# Communication.net
KiCad netlist of a schematic drawn in Altium Designer
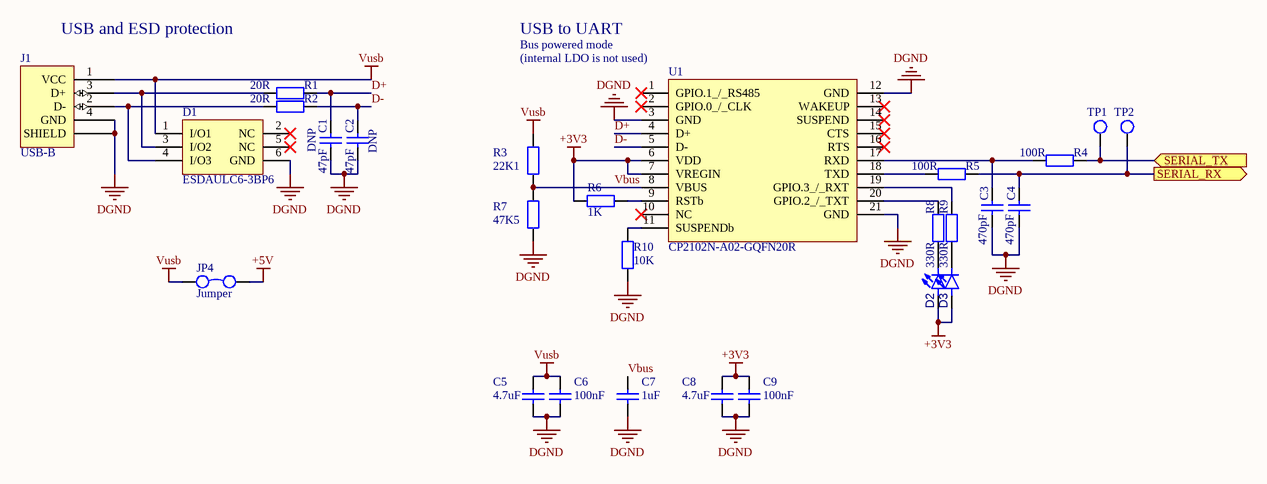
[diagram p0: Communication.SchDoc]

(export (version "E")
  (design (tool "Eeschema 10.0.6"))
  (components
    (comp (ref "C1")
      (value "DNP")
      (footprint "CAP0603")
      (fields
        (field (name "MANUFACTURER") "KEMET")
        (field (name "MANUFACTURER PART NUMBER") "C0603C470J1GACTU")
        (field (name "ALTIUM_VALUE") "47pF")
      )
      (libsource (lib "UPS_Schlib") (part "47pF"))
    )
    (comp (ref "C2")
      (value "DNP")
      (footprint "CAP0603")
      (fields
        (field (name "MANUFACTURER") "KEMET")
        (field (name "MANUFACTURER PART NUMBER") "C0603C470J1GACTU")
        (field (name "ALTIUM_VALUE") "47pF")
      )
      (libsource (lib "UPS_Schlib") (part "47pF"))
    )
    (comp (ref "C3")
      (value "470pF")
      (footprint "CAP0603")
      (fields
        (field (name "MANUFACTURER") "KEMET")
        (field (name "MANUFACTURER PART NUMBER") "C0603C471JAGACAUTO")
      )
      (libsource (lib "UPS_Schlib") (part "470pF"))
    )
    (comp (ref "C4")
      (value "470pF")
      (footprint "CAP0603")
      (fields
        (field (name "MANUFACTURER") "KEMET")
        (field (name "MANUFACTURER PART NUMBER") "C0603C471JAGACAUTO")
      )
      (libsource (lib "UPS_Schlib") (part "470pF"))
    )
    (comp (ref "C5")
      (value "4.7uF")
      (footprint "CAP0603")
      (description "Capacitor")
      (libsource (lib "UPS_Schlib") (part "4.7uF"))
    )
    (comp (ref "C6")
      (value "100nF")
      (footprint "CAP0603")
      (description "Capacitor")
      (libsource (lib "UPS_Schlib") (part "100nF"))
    )
    (comp (ref "C7")
      (value "1uF")
      (footprint "CAP0603")
      (description "Capacitor")
      (libsource (lib "UPS_Schlib") (part "1uF"))
    )
    (comp (ref "C8")
      (value "4.7uF")
      (footprint "CAP0603")
      (description "Capacitor")
      (libsource (lib "UPS_Schlib") (part "4.7uF"))
    )
    (comp (ref "C9")
      (value "100nF")
      (footprint "CAP0603")
      (description "Capacitor")
      (libsource (lib "UPS_Schlib") (part "100nF"))
    )
    (comp (ref "D1")
      (value "ESDAULC6-3BP6")
      (footprint "SOT-666")
      (description "TVS Diode (Bi-directional)")
      (fields (field (name "MOUSER PART NUMBER") "511-ESDAULC63BP6"))
      (libsource (lib "UPS_Schlib") (part "ESDAULC6-3BP6"))
    )
    (comp (ref "D2")
      (value "~")
      (footprint "LED0603")
      (description "Single Color LED, Bright Green, Water Clear, 1.1mm")
      (fields
        (field (name "MANUFACTURER") "Wurth Electronics")
        (field (name "MANUFACTURER PART NUMBER") "150060VS75000")
      )
      (libsource (lib "UPS_Schlib") (part "LED Green"))
    )
    (comp (ref "D3")
      (value "~")
      (footprint "LED0603")
      (description "Single Color LED, Bright Green, Water Clear, 1.1mm")
      (fields
        (field (name "MANUFACTURER") "Wurth Electronics")
        (field (name "MANUFACTURER PART NUMBER") "150060VS75000")
      )
      (libsource (lib "UPS_Schlib") (part "LED Green"))
    )
    (comp (ref "J1")
      (value "USB-B")
      (footprint "USB-B-FEMALE")
      (description "USB Connector")
      (libsource (lib "UPS_Schlib") (part "USB-B"))
    )
    (comp (ref "JP4")
      (value "Jumper")
      (footprint "PIN-1X2")
      (description "2 pin jumper connection")
      (libsource (lib "UPS_Schlib") (part "Jumper"))
    )
    (comp (ref "R1")
      (value "20R")
      (footprint "RES0603")
      (description "Resistor")
      (libsource (lib "UPS_Schlib") (part "20R"))
    )
    (comp (ref "R2")
      (value "20R")
      (footprint "RES0603")
      (description "Resistor")
      (libsource (lib "UPS_Schlib") (part "20R"))
    )
    (comp (ref "R3")
      (value "22K1")
      (footprint "RES0603")
      (description "Resistor")
      (libsource (lib "UPS_Schlib") (part "22K1"))
    )
    (comp (ref "R4")
      (value "100R")
      (footprint "RES0603")
      (description "Resistor")
      (libsource (lib "UPS_Schlib") (part "100R"))
    )
    (comp (ref "R5")
      (value "100R")
      (footprint "RES0603")
      (description "Resistor")
      (libsource (lib "UPS_Schlib") (part "100R"))
    )
    (comp (ref "R6")
      (value "1K")
      (footprint "RES0603")
      (description "Resistor")
      (libsource (lib "UPS_Schlib") (part "1K"))
    )
    (comp (ref "R7")
      (value "47K5")
      (footprint "RES0603")
      (description "Resistor")
      (libsource (lib "UPS_Schlib") (part "47K5"))
    )
    (comp (ref "R8")
      (value "330R")
      (footprint "RES0603")
      (description "Resistor")
      (libsource (lib "UPS_Schlib") (part "330R"))
    )
    (comp (ref "R9")
      (value "330R")
      (footprint "RES0603")
      (description "Resistor")
      (libsource (lib "UPS_Schlib") (part "330R"))
    )
    (comp (ref "R10")
      (value "10K")
      (footprint "RES0603")
      (description "Resistor")
      (libsource (lib "UPS_Schlib") (part "10K"))
    )
    (comp (ref "TP1")
      (value "Test Point")
      (footprint "TP-1.5HOLE")
      (libsource (lib "UPS_Schlib") (part "Test Point"))
    )
    (comp (ref "TP2")
      (value "Test Point")
      (footprint "TP-1.5HOLE")
      (libsource (lib "UPS_Schlib") (part "Test Point"))
    )
    (comp (ref "U1")
      (value "CP2102N-A02-GQFN20R")
      (footprint "QFN-20")
      (description "USB-UART Bridge")
      (fields (field (name "MOUSER PART NUMBER") "634-CP2102NA02QFN20R"))
      (libsource (lib "UPS_Schlib") (part "CP2102N-A02-GQFN20R"))
    )
  )
  (nets
    (net (code "1") (name "+3V3") (class "Default")
      (node (ref "C8") (pin "2") (pinfunction "2_2") (pintype "passive"))
      (node (ref "C9") (pin "1") (pinfunction "1_1") (pintype "passive"))
      (node (ref "D2") (pin "2") (pinfunction "A_2") (pintype "passive"))
      (node (ref "D3") (pin "2") (pinfunction "A_2") (pintype "passive"))
      (node (ref "R6") (pin "1") (pinfunction "1_1") (pintype "passive"))
      (node (ref "U1") (pin "6") (pinfunction "VDD_6") (pintype "passive"))
      (node (ref "U1") (pin "7") (pinfunction "VREGIN_7") (pintype "passive"))
    )
    (net (code "2") (name "+5V") (class "Default") (node (ref "JP4") (pin "2") (pintype "passive")))
    (net (code "3") (name "/D+") (class "Default")
      (node (ref "C1") (pin "2") (pinfunction "2_2") (pintype "passive"))
      (node (ref "R1") (pin "1") (pinfunction "1_1") (pintype "passive"))
      (node (ref "U1") (pin "4") (pinfunction "D+_4") (pintype "passive"))
    )
    (net (code "4") (name "/D-") (class "Default")
      (node (ref "C2") (pin "2") (pinfunction "2_2") (pintype "passive"))
      (node (ref "R2") (pin "1") (pinfunction "1_1") (pintype "passive"))
      (node (ref "U1") (pin "5") (pinfunction "D-_5") (pintype "passive"))
    )
    (net (code "5") (name "/SERIAL_RX") (class "Default")
      (node (ref "C4") (pin "2") (pinfunction "2_2") (pintype "passive"))
      (node (ref "R5") (pin "2") (pinfunction "2_2") (pintype "passive"))
      (node (ref "TP2") (pin "1") (pintype "passive"))
    )
    (net (code "6") (name "/SERIAL_TX") (class "Default")
      (node (ref "R4") (pin "2") (pinfunction "2_2") (pintype "passive"))
      (node (ref "TP1") (pin "1") (pintype "passive"))
    )
    (net (code "7") (name "/Vbus") (class "Default")
      (node (ref "C7") (pin "2") (pinfunction "2_2") (pintype "passive"))
      (node (ref "R3") (pin "1") (pinfunction "1_1") (pintype "passive"))
      (node (ref "R7") (pin "2") (pinfunction "2_2") (pintype "passive"))
      (node (ref "U1") (pin "8") (pinfunction "VBUS_8") (pintype "passive"))
    )
    (net (code "8") (name "DGND") (class "Default")
      (node (ref "C1") (pin "1") (pinfunction "1_1") (pintype "passive"))
      (node (ref "C2") (pin "1") (pinfunction "1_1") (pintype "passive"))
      (node (ref "C3") (pin "1") (pinfunction "1_1") (pintype "passive"))
      (node (ref "C4") (pin "1") (pinfunction "1_1") (pintype "passive"))
      (node (ref "C5") (pin "1") (pinfunction "1_1") (pintype "passive"))
      (node (ref "C6") (pin "2") (pinfunction "2_2") (pintype "passive"))
      (node (ref "C7") (pin "1") (pinfunction "1_1") (pintype "passive"))
      (node (ref "C8") (pin "1") (pinfunction "1_1") (pintype "passive"))
      (node (ref "C9") (pin "2") (pinfunction "2_2") (pintype "passive"))
      (node (ref "D1") (pin "6") (pinfunction "GND_6") (pintype "passive"))
      (node (ref "J1") (pin "0") (pinfunction "SHIELD_0") (pintype "passive"))
      (node (ref "J1") (pin "4") (pinfunction "GND_4") (pintype "passive"))
      (node (ref "R10") (pin "1") (pinfunction "1_1") (pintype "passive"))
      (node (ref "R7") (pin "1") (pinfunction "1_1") (pintype "passive"))
      (node (ref "U1") (pin "12") (pinfunction "GND_12") (pintype "passive"))
      (node (ref "U1") (pin "21") (pinfunction "GND_21") (pintype "passive"))
      (node (ref "U1") (pin "3") (pinfunction "GND_3") (pintype "passive"))
    )
    (net (code "9") (name "Net-(D1-I{slash}O2)") (class "Default")
      (node (ref "D1") (pin "3") (pinfunction "I/O2_3") (pintype "passive"))
      (node (ref "J1") (pin "3") (pinfunction "D+_3") (pintype "bidirectional"))
      (node (ref "R1") (pin "2") (pinfunction "2_2") (pintype "passive"))
    )
    (net (code "10") (name "Net-(D1-I{slash}O3)") (class "Default")
      (node (ref "D1") (pin "4") (pinfunction "I/O3_4") (pintype "passive"))
      (node (ref "J1") (pin "2") (pinfunction "D-_2") (pintype "bidirectional"))
      (node (ref "R2") (pin "2") (pinfunction "2_2") (pintype "passive"))
    )
    (net (code "11") (name "Net-(D2-K)") (class "Default")
      (node (ref "D2") (pin "1") (pinfunction "K_1") (pintype "passive"))
      (node (ref "R8") (pin "2") (pinfunction "2_2") (pintype "passive"))
    )
    (net (code "12") (name "Net-(D3-K)") (class "Default")
      (node (ref "D3") (pin "1") (pinfunction "K_1") (pintype "passive"))
      (node (ref "R9") (pin "2") (pinfunction "2_2") (pintype "passive"))
    )
    (net (code "13") (name "Net-(U1-GPIO.2_{slash}_TXT)") (class "Default")
      (node (ref "R8") (pin "1") (pinfunction "1_1") (pintype "passive"))
      (node (ref "U1") (pin "20") (pinfunction "GPIO.2_/_TXT_20") (pintype "passive"))
    )
    (net (code "14") (name "Net-(U1-GPIO.3_{slash}_RXT)") (class "Default")
      (node (ref "R9") (pin "1") (pinfunction "1_1") (pintype "passive"))
      (node (ref "U1") (pin "19") (pinfunction "GPIO.3_/_RXT_19") (pintype "passive"))
    )
    (net (code "15") (name "Net-(U1-RSTb)") (class "Default")
      (node (ref "R6") (pin "2") (pinfunction "2_2") (pintype "passive"))
      (node (ref "U1") (pin "9") (pinfunction "RSTb_9") (pintype "passive"))
    )
    (net (code "16") (name "Net-(U1-RXD)") (class "Default")
      (node (ref "C3") (pin "2") (pinfunction "2_2") (pintype "passive"))
      (node (ref "R4") (pin "1") (pinfunction "1_1") (pintype "passive"))
      (node (ref "U1") (pin "17") (pinfunction "RXD_17") (pintype "passive"))
    )
    (net (code "17") (name "Net-(U1-SUSPENDb)") (class "Default")
      (node (ref "R10") (pin "2") (pinfunction "2_2") (pintype "passive"))
      (node (ref "U1") (pin "11") (pinfunction "SUSPENDb_11") (pintype "passive"))
    )
    (net (code "18") (name "Net-(U1-TXD)") (class "Default")
      (node (ref "R5") (pin "1") (pinfunction "1_1") (pintype "passive"))
      (node (ref "U1") (pin "18") (pinfunction "TXD_18") (pintype "passive"))
    )
    (net (code "19") (name "Vusb") (class "Default")
      (node (ref "C5") (pin "2") (pinfunction "2_2") (pintype "passive"))
      (node (ref "C6") (pin "1") (pinfunction "1_1") (pintype "passive"))
      (node (ref "D1") (pin "1") (pinfunction "I/O1_1") (pintype "passive"))
      (node (ref "J1") (pin "1") (pinfunction "VCC_1") (pintype "power_in"))
      (node (ref "JP4") (pin "1") (pintype "passive"))
      (node (ref "R3") (pin "2") (pinfunction "2_2") (pintype "passive"))
    )
    (net (code "20") (name "unconnected-(D1-NC-Pad2)") (class "Default")
      (node (ref "D1") (pin "2") (pinfunction "NC_2") (pintype "passive+no_connect"))
    )
    (net (code "21") (name "unconnected-(D1-NC-Pad5)") (class "Default")
      (node (ref "D1") (pin "5") (pinfunction "NC_5") (pintype "passive+no_connect"))
    )
    (net (code "22") (name "unconnected-(U1-CTS-Pad15)") (class "Default")
      (node (ref "U1") (pin "15") (pinfunction "CTS_15") (pintype "passive+no_connect"))
    )
    (net (code "23") (name "unconnected-(U1-GPIO.0_{slash}_CLK-Pad2)") (class "Default")
      (node (ref "U1") (pin "2") (pinfunction "GPIO.0_/_CLK_2") (pintype "passive+no_connect"))
    )
    (net (code "24") (name "unconnected-(U1-GPIO.1_{slash}_RS485-Pad1)") (class "Default")
      (node (ref "U1") (pin "1") (pinfunction "GPIO.1_/_RS485_1") (pintype "passive+no_connect"))
    )
    (net (code "25") (name "unconnected-(U1-NC-Pad10)") (class "Default")
      (node (ref "U1") (pin "10") (pinfunction "NC_10") (pintype "passive+no_connect"))
    )
    (net (code "26") (name "unconnected-(U1-RTS-Pad16)") (class "Default")
      (node (ref "U1") (pin "16") (pinfunction "RTS_16") (pintype "passive+no_connect"))
    )
    (net (code "27") (name "unconnected-(U1-SUSPEND-Pad14)") (class "Default")
      (node (ref "U1") (pin "14") (pinfunction "SUSPEND_14") (pintype "passive+no_connect"))
    )
    (net (code "28") (name "unconnected-(U1-WAKEUP-Pad13)") (class "Default")
      (node (ref "U1") (pin "13") (pinfunction "WAKEUP_13") (pintype "passive+no_connect"))
    )
  )
)
